# 05_-_MECHANICAL.net
KiCad netlist of a schematic drawn in Altium Designer
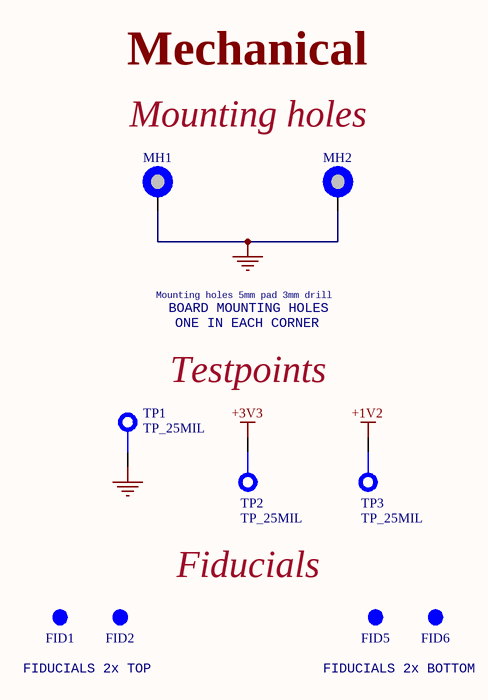
[diagram p0: [05] - MECHANICAL.SchDoc]

(export (version "E")
  (design (tool "Eeschema 10.0.6"))
  (components
    (comp (ref "FID1")
      (value "FID_40x120")
      (footprint "FID_40x120")
      (description "Fiducial")
      (libsource (lib "JAVI_LIB") (part "FID_40x120"))
    )
    (comp (ref "FID2")
      (value "FID_40x120")
      (footprint "FID_40x120")
      (description "Fiducial")
      (libsource (lib "JAVI_LIB") (part "FID_40x120"))
    )
    (comp (ref "FID5")
      (value "FID_40x120")
      (footprint "FID_40x120")
      (description "Fiducial")
      (libsource (lib "JAVI_LIB") (part "FID_40x120"))
    )
    (comp (ref "FID6")
      (value "FID_40x120")
      (footprint "FID_40x120")
      (description "Fiducial")
      (libsource (lib "JAVI_LIB") (part "FID_40x120"))
    )
    (comp (ref "MH1")
      (value "Mounting Hole")
      (footprint "GUILLETRONIC:MH3")
      (libsource (lib "JAVI_LIB") (part "MH5"))
    )
    (comp (ref "MH2") (value "Mounting Hole") (footprint "MH3") (libsource (lib "JAVI_LIB") (part "MH5")))
    (comp (ref "TP1")
      (value "TP_25MIL")
      (footprint "TP_25MIL")
      (description "Test Point 25mil")
      (libsource (lib "JAVI_LIB") (part "TP_25MIL"))
    )
    (comp (ref "TP2")
      (value "TP_25MIL")
      (footprint "TP_25MIL")
      (description "Test Point 25mil")
      (libsource (lib "JAVI_LIB") (part "TP_25MIL"))
    )
    (comp (ref "TP3")
      (value "TP_25MIL")
      (footprint "TP_25MIL")
      (description "Test Point 25mil")
      (libsource (lib "JAVI_LIB") (part "TP_25MIL"))
    )
  )
  (nets
    (net (code "1") (name "+1V2") (class "Default")
      (node (ref "TP3") (pin "1") (pinfunction "1_1") (pintype "power_in"))
    )
    (net (code "2") (name "+3V3") (class "Default")
      (node (ref "TP2") (pin "1") (pinfunction "1_1") (pintype "power_in"))
    )
    (net (code "3") (name "GND") (class "Default")
      (node (ref "MH1") (pin "1") (pinfunction "1_1") (pintype "power_in"))
      (node (ref "MH2") (pin "1") (pinfunction "1_1") (pintype "power_in"))
      (node (ref "TP1") (pin "1") (pinfunction "1_1") (pintype "power_in"))
    )
  )
)
